# eight-channel-ina2128-afe.net
KiCad netlist of a schematic drawn in Altium Designer
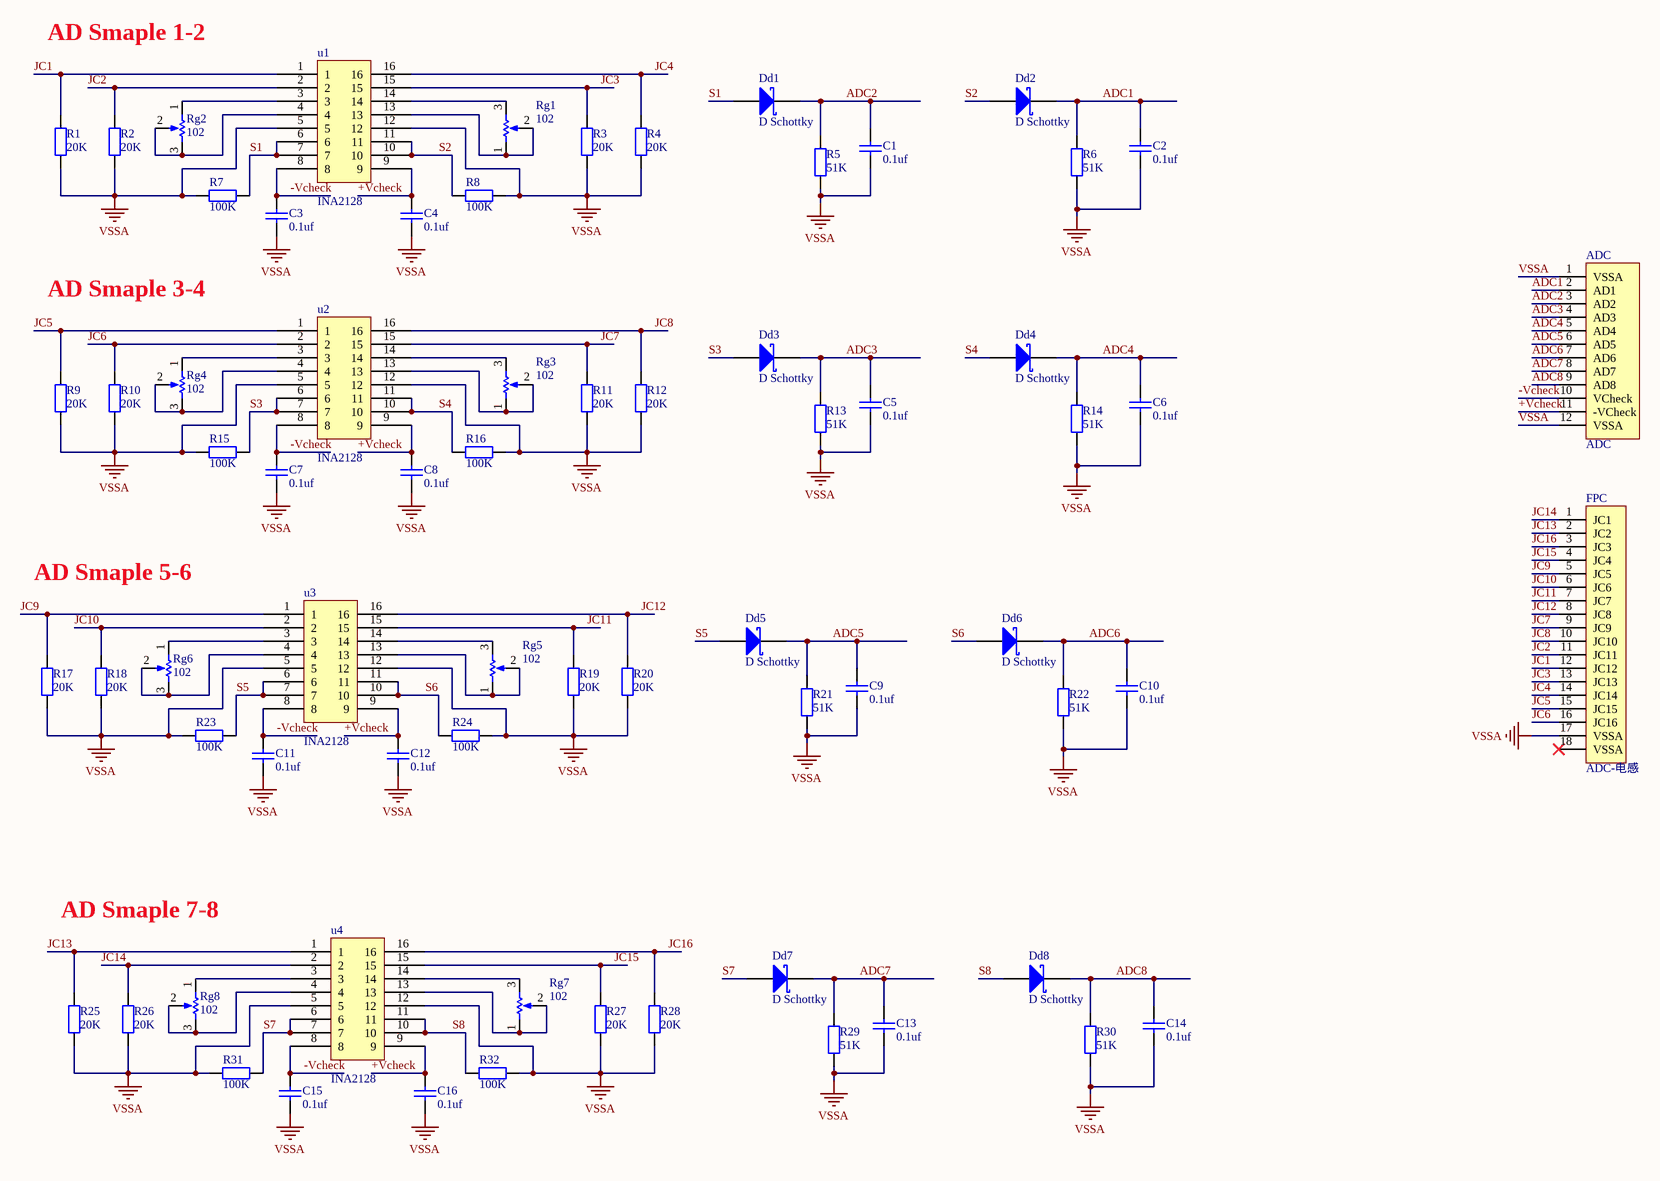
[diagram p0: eight-channel-ina2128-afe.SchDoc]

(export (version "E")
  (design (tool "Eeschema 10.0.6"))
  (components
    (comp (ref "ADC") (value "ADC") (footprint "FPC0.5 2H-WS-12P") (libsource (lib "my_DXP") (part "ADC")))
    (comp (ref "C1") (value "0.1uf") (footprint "LC-0603_C") (libsource (lib "my_DXP") (part "Cap")))
    (comp (ref "C2") (value "0.1uf") (footprint "LC-0603_C") (libsource (lib "my_DXP") (part "Cap")))
    (comp (ref "C3") (value "0.1uf") (footprint "LC-0603_C") (libsource (lib "my_DXP") (part "Cap")))
    (comp (ref "C4") (value "0.1uf") (footprint "LC-0603_C") (libsource (lib "my_DXP") (part "Cap")))
    (comp (ref "C5") (value "0.1uf") (footprint "LC-0603_C") (libsource (lib "my_DXP") (part "Cap")))
    (comp (ref "C6") (value "0.1uf") (footprint "LC-0603_C") (libsource (lib "my_DXP") (part "Cap")))
    (comp (ref "C7") (value "0.1uf") (footprint "LC-0603_C") (libsource (lib "my_DXP") (part "Cap")))
    (comp (ref "C8") (value "0.1uf") (footprint "LC-0603_C") (libsource (lib "my_DXP") (part "Cap")))
    (comp (ref "C9") (value "0.1uf") (footprint "LC-0603_C") (libsource (lib "my_DXP") (part "Cap")))
    (comp (ref "C10") (value "0.1uf") (footprint "LC-0603_C") (libsource (lib "my_DXP") (part "Cap")))
    (comp (ref "C11") (value "0.1uf") (footprint "LC-0603_C") (libsource (lib "my_DXP") (part "Cap")))
    (comp (ref "C12") (value "0.1uf") (footprint "LC-0603_C") (libsource (lib "my_DXP") (part "Cap")))
    (comp (ref "C13") (value "0.1uf") (footprint "LC-0603_C") (libsource (lib "my_DXP") (part "Cap")))
    (comp (ref "C14") (value "0.1uf") (footprint "LC-0603_C") (libsource (lib "my_DXP") (part "Cap")))
    (comp (ref "C15") (value "0.1uf") (footprint "LC-0603_C") (libsource (lib "my_DXP") (part "Cap")))
    (comp (ref "C16") (value "0.1uf") (footprint "LC-0603_C") (libsource (lib "my_DXP") (part "Cap")))
    (comp (ref "Dd1")
      (value "D Schottky")
      (footprint "SOD-323")
      (description "Schottky Diode")
      (fields (field (name "PUBLISHER") "Altium Limited"))
      (libsource (lib "my_DXP") (part "D Schottky"))
    )
    (comp (ref "Dd2")
      (value "D Schottky")
      (footprint "SOD-323")
      (description "Schottky Diode")
      (fields (field (name "PUBLISHER") "Altium Limited"))
      (libsource (lib "my_DXP") (part "D Schottky"))
    )
    (comp (ref "Dd3")
      (value "D Schottky")
      (footprint "SOD-323")
      (description "Schottky Diode")
      (fields (field (name "PUBLISHER") "Altium Limited"))
      (libsource (lib "my_DXP") (part "D Schottky"))
    )
    (comp (ref "Dd4")
      (value "D Schottky")
      (footprint "SOD-323")
      (description "Schottky Diode")
      (fields (field (name "PUBLISHER") "Altium Limited"))
      (libsource (lib "my_DXP") (part "D Schottky"))
    )
    (comp (ref "Dd5")
      (value "D Schottky")
      (footprint "SOD-323")
      (description "Schottky Diode")
      (fields (field (name "PUBLISHER") "Altium Limited"))
      (libsource (lib "my_DXP") (part "D Schottky"))
    )
    (comp (ref "Dd6")
      (value "D Schottky")
      (footprint "SOD-323")
      (description "Schottky Diode")
      (fields (field (name "PUBLISHER") "Altium Limited"))
      (libsource (lib "my_DXP") (part "D Schottky"))
    )
    (comp (ref "Dd7")
      (value "D Schottky")
      (footprint "SOD-323")
      (description "Schottky Diode")
      (fields (field (name "PUBLISHER") "Altium Limited"))
      (libsource (lib "my_DXP") (part "D Schottky"))
    )
    (comp (ref "Dd8")
      (value "D Schottky")
      (footprint "SOD-323")
      (description "Schottky Diode")
      (fields (field (name "PUBLISHER") "Altium Limited"))
      (libsource (lib "my_DXP") (part "D Schottky"))
    )
    (comp (ref "FPC") (value "ADC-电感") (footprint "fpc_0.5_16pin") (libsource (lib "my_DXP") (part "ADC-电感")))
    (comp (ref "R1")
      (value "20K")
      (footprint "LC-0603_R")
      (description "Resistor")
      (fields (field (name "Comment") "20k") (field (name "PUBLISHER") "Altium Limited"))
      (libsource (lib "my_DXP") (part "Res"))
    )
    (comp (ref "R2")
      (value "20K")
      (footprint "LC-0603_R")
      (description "Resistor")
      (fields (field (name "Comment") "20k") (field (name "PUBLISHER") "Altium Limited"))
      (libsource (lib "my_DXP") (part "Res"))
    )
    (comp (ref "R3")
      (value "20K")
      (footprint "LC-0603_R")
      (description "Resistor")
      (fields (field (name "Comment") "20k") (field (name "PUBLISHER") "Altium Limited"))
      (libsource (lib "my_DXP") (part "Res"))
    )
    (comp (ref "R4")
      (value "20K")
      (footprint "LC-0603_R")
      (description "Resistor")
      (fields (field (name "Comment") "20k") (field (name "PUBLISHER") "Altium Limited"))
      (libsource (lib "my_DXP") (part "Res"))
    )
    (comp (ref "R5")
      (value "51K")
      (footprint "LC-0603_R")
      (description "Resistor")
      (fields (field (name "Comment") "20k") (field (name "PUBLISHER") "Altium Limited"))
      (libsource (lib "my_DXP") (part "Res"))
    )
    (comp (ref "R6")
      (value "51K")
      (footprint "LC-0603_R")
      (description "Resistor")
      (fields (field (name "Comment") "20k") (field (name "PUBLISHER") "Altium Limited"))
      (libsource (lib "my_DXP") (part "Res"))
    )
    (comp (ref "R7")
      (value "100K")
      (footprint "LC-0603_R")
      (description "Resistor")
      (fields (field (name "Comment") "100k") (field (name "PUBLISHER") "Altium Limited"))
      (libsource (lib "") (part "Res_1"))
    )
    (comp (ref "R8")
      (value "100K")
      (footprint "LC-0603_R")
      (description "Resistor")
      (fields (field (name "Comment") "100k") (field (name "PUBLISHER") "Altium Limited"))
      (libsource (lib "") (part "Res_1"))
    )
    (comp (ref "R9")
      (value "20K")
      (footprint "LC-0603_R")
      (description "Resistor")
      (fields (field (name "Comment") "20k") (field (name "PUBLISHER") "Altium Limited"))
      (libsource (lib "my_DXP") (part "Res"))
    )
    (comp (ref "R10")
      (value "20K")
      (footprint "LC-0603_R")
      (description "Resistor")
      (fields (field (name "Comment") "20k") (field (name "PUBLISHER") "Altium Limited"))
      (libsource (lib "my_DXP") (part "Res"))
    )
    (comp (ref "R11")
      (value "20K")
      (footprint "LC-0603_R")
      (description "Resistor")
      (fields (field (name "Comment") "20k") (field (name "PUBLISHER") "Altium Limited"))
      (libsource (lib "my_DXP") (part "Res"))
    )
    (comp (ref "R12")
      (value "20K")
      (footprint "LC-0603_R")
      (description "Resistor")
      (fields (field (name "Comment") "20k") (field (name "PUBLISHER") "Altium Limited"))
      (libsource (lib "my_DXP") (part "Res"))
    )
    (comp (ref "R13")
      (value "51K")
      (footprint "LC-0603_R")
      (description "Resistor")
      (fields (field (name "Comment") "20k") (field (name "PUBLISHER") "Altium Limited"))
      (libsource (lib "my_DXP") (part "Res"))
    )
    (comp (ref "R14")
      (value "51K")
      (footprint "LC-0603_R")
      (description "Resistor")
      (fields (field (name "Comment") "20k") (field (name "PUBLISHER") "Altium Limited"))
      (libsource (lib "my_DXP") (part "Res"))
    )
    (comp (ref "R15")
      (value "100K")
      (footprint "LC-0603_R")
      (description "Resistor")
      (fields (field (name "Comment") "100k") (field (name "PUBLISHER") "Altium Limited"))
      (libsource (lib "") (part "Res_1"))
    )
    (comp (ref "R16")
      (value "100K")
      (footprint "LC-0603_R")
      (description "Resistor")
      (fields (field (name "Comment") "100k") (field (name "PUBLISHER") "Altium Limited"))
      (libsource (lib "") (part "Res_1"))
    )
    (comp (ref "R17")
      (value "20K")
      (footprint "LC-0603_R")
      (description "Resistor")
      (fields (field (name "Comment") "20k") (field (name "PUBLISHER") "Altium Limited"))
      (libsource (lib "my_DXP") (part "Res"))
    )
    (comp (ref "R18")
      (value "20K")
      (footprint "LC-0603_R")
      (description "Resistor")
      (fields (field (name "Comment") "20k") (field (name "PUBLISHER") "Altium Limited"))
      (libsource (lib "my_DXP") (part "Res"))
    )
    (comp (ref "R19")
      (value "20K")
      (footprint "LC-0603_R")
      (description "Resistor")
      (fields (field (name "Comment") "20k") (field (name "PUBLISHER") "Altium Limited"))
      (libsource (lib "my_DXP") (part "Res"))
    )
    (comp (ref "R20")
      (value "20K")
      (footprint "LC-0603_R")
      (description "Resistor")
      (fields (field (name "Comment") "20k") (field (name "PUBLISHER") "Altium Limited"))
      (libsource (lib "my_DXP") (part "Res"))
    )
    (comp (ref "R21")
      (value "51K")
      (footprint "LC-0603_R")
      (description "Resistor")
      (fields (field (name "Comment") "20k") (field (name "PUBLISHER") "Altium Limited"))
      (libsource (lib "my_DXP") (part "Res"))
    )
    (comp (ref "R22")
      (value "51K")
      (footprint "LC-0603_R")
      (description "Resistor")
      (fields (field (name "Comment") "20k") (field (name "PUBLISHER") "Altium Limited"))
      (libsource (lib "my_DXP") (part "Res"))
    )
    (comp (ref "R23")
      (value "100K")
      (footprint "LC-0603_R")
      (description "Resistor")
      (fields (field (name "Comment") "100k") (field (name "PUBLISHER") "Altium Limited"))
      (libsource (lib "") (part "Res_1"))
    )
    (comp (ref "R24")
      (value "100K")
      (footprint "LC-0603_R")
      (description "Resistor")
      (fields (field (name "Comment") "100k") (field (name "PUBLISHER") "Altium Limited"))
      (libsource (lib "") (part "Res_1"))
    )
    (comp (ref "R25")
      (value "20K")
      (footprint "LC-0603_R")
      (description "Resistor")
      (fields (field (name "Comment") "20k") (field (name "PUBLISHER") "Altium Limited"))
      (libsource (lib "my_DXP") (part "Res"))
    )
    (comp (ref "R26")
      (value "20K")
      (footprint "LC-0603_R")
      (description "Resistor")
      (fields (field (name "Comment") "20k") (field (name "PUBLISHER") "Altium Limited"))
      (libsource (lib "my_DXP") (part "Res"))
    )
    (comp (ref "R27")
      (value "20K")
      (footprint "LC-0603_R")
      (description "Resistor")
      (fields (field (name "Comment") "20k") (field (name "PUBLISHER") "Altium Limited"))
      (libsource (lib "my_DXP") (part "Res"))
    )
    (comp (ref "R28")
      (value "20K")
      (footprint "LC-0603_R")
      (description "Resistor")
      (fields (field (name "Comment") "20k") (field (name "PUBLISHER") "Altium Limited"))
      (libsource (lib "my_DXP") (part "Res"))
    )
    (comp (ref "R29")
      (value "51K")
      (footprint "LC-0603_R")
      (description "Resistor")
      (fields (field (name "Comment") "20k") (field (name "PUBLISHER") "Altium Limited"))
      (libsource (lib "my_DXP") (part "Res"))
    )
    (comp (ref "R30")
      (value "51K")
      (footprint "LC-0603_R")
      (description "Resistor")
      (fields (field (name "Comment") "20k") (field (name "PUBLISHER") "Altium Limited"))
      (libsource (lib "my_DXP") (part "Res"))
    )
    (comp (ref "R31")
      (value "100K")
      (footprint "LC-0603_R")
      (description "Resistor")
      (fields (field (name "Comment") "100k") (field (name "PUBLISHER") "Altium Limited"))
      (libsource (lib "") (part "Res_1"))
    )
    (comp (ref "R32")
      (value "100K")
      (footprint "LC-0603_R")
      (description "Resistor")
      (fields (field (name "Comment") "100k") (field (name "PUBLISHER") "Altium Limited"))
      (libsource (lib "") (part "Res_1"))
    )
    (comp (ref "Rg1")
      (value "102")
      (footprint "精密电位器")
      (description "Potentiometer")
      (fields (field (name "PUBLISHER") "Altium Limited"))
      (libsource (lib "my_DXP") (part "RPot"))
    )
    (comp (ref "Rg2")
      (value "102")
      (footprint "精密电位器")
      (description "Potentiometer")
      (fields (field (name "PUBLISHER") "Altium Limited"))
      (libsource (lib "my_DXP") (part "RPot"))
    )
    (comp (ref "Rg3")
      (value "102")
      (footprint "精密电位器")
      (description "Potentiometer")
      (fields (field (name "PUBLISHER") "Altium Limited"))
      (libsource (lib "my_DXP") (part "RPot"))
    )
    (comp (ref "Rg4")
      (value "102")
      (footprint "精密电位器")
      (description "Potentiometer")
      (fields (field (name "PUBLISHER") "Altium Limited"))
      (libsource (lib "my_DXP") (part "RPot"))
    )
    (comp (ref "Rg5")
      (value "102")
      (footprint "精密电位器")
      (description "Potentiometer")
      (fields (field (name "PUBLISHER") "Altium Limited"))
      (libsource (lib "my_DXP") (part "RPot"))
    )
    (comp (ref "Rg6")
      (value "102")
      (footprint "精密电位器")
      (description "Potentiometer")
      (fields (field (name "PUBLISHER") "Altium Limited"))
      (libsource (lib "my_DXP") (part "RPot"))
    )
    (comp (ref "Rg7")
      (value "102")
      (footprint "精密电位器")
      (description "Potentiometer")
      (fields (field (name "PUBLISHER") "Altium Limited"))
      (libsource (lib "my_DXP") (part "RPot"))
    )
    (comp (ref "Rg8")
      (value "102")
      (footprint "精密电位器")
      (description "Potentiometer")
      (fields (field (name "PUBLISHER") "Altium Limited"))
      (libsource (lib "my_DXP") (part "RPot"))
    )
    (comp (ref "u1") (value "INA2128") (footprint "INA2128") (libsource (lib "my_DXP") (part "INA2128")))
    (comp (ref "u2") (value "INA2128") (footprint "INA2128") (libsource (lib "my_DXP") (part "INA2128")))
    (comp (ref "u3") (value "INA2128") (footprint "INA2128") (libsource (lib "my_DXP") (part "INA2128")))
    (comp (ref "u4") (value "INA2128") (footprint "INA2128") (libsource (lib "my_DXP") (part "INA2128")))
  )
  (nets
    (net (code "1") (name "/+Vcheck") (class "Default")
      (node (ref "ADC") (pin "11") (pinfunction "-VCheck_11") (pintype "passive"))
      (node (ref "C12") (pin "2") (pinfunction "2_2") (pintype "passive"))
      (node (ref "C16") (pin "2") (pinfunction "2_2") (pintype "passive"))
      (node (ref "C4") (pin "2") (pinfunction "2_2") (pintype "passive"))
      (node (ref "C8") (pin "2") (pinfunction "2_2") (pintype "passive"))
      (node (ref "u1") (pin "9") (pinfunction "9_9") (pintype "passive"))
      (node (ref "u2") (pin "9") (pinfunction "9_9") (pintype "passive"))
      (node (ref "u3") (pin "9") (pinfunction "9_9") (pintype "passive"))
      (node (ref "u4") (pin "9") (pinfunction "9_9") (pintype "passive"))
    )
    (net (code "2") (name "/-Vcheck") (class "Default")
      (node (ref "ADC") (pin "10") (pinfunction "VCheck_10") (pintype "passive"))
      (node (ref "C11") (pin "2") (pinfunction "2_2") (pintype "passive"))
      (node (ref "C15") (pin "2") (pinfunction "2_2") (pintype "passive"))
      (node (ref "C3") (pin "2") (pinfunction "2_2") (pintype "passive"))
      (node (ref "C7") (pin "2") (pinfunction "2_2") (pintype "passive"))
      (node (ref "u1") (pin "8") (pinfunction "8_8") (pintype "passive"))
      (node (ref "u2") (pin "8") (pinfunction "8_8") (pintype "passive"))
      (node (ref "u3") (pin "8") (pinfunction "8_8") (pintype "passive"))
      (node (ref "u4") (pin "8") (pinfunction "8_8") (pintype "passive"))
    )
    (net (code "3") (name "/ADC1") (class "Default")
      (node (ref "ADC") (pin "2") (pinfunction "AD1_2") (pintype "passive"))
      (node (ref "C2") (pin "2") (pinfunction "2_2") (pintype "passive"))
      (node (ref "Dd2") (pin "2") (pinfunction "K_2") (pintype "passive"))
      (node (ref "R6") (pin "1") (pinfunction "1_1") (pintype "passive"))
    )
    (net (code "4") (name "/ADC2") (class "Default")
      (node (ref "ADC") (pin "3") (pinfunction "AD2_3") (pintype "passive"))
      (node (ref "C1") (pin "2") (pinfunction "2_2") (pintype "passive"))
      (node (ref "Dd1") (pin "2") (pinfunction "K_2") (pintype "passive"))
      (node (ref "R5") (pin "1") (pinfunction "1_1") (pintype "passive"))
    )
    (net (code "5") (name "/ADC3") (class "Default")
      (node (ref "ADC") (pin "4") (pinfunction "AD3_4") (pintype "passive"))
      (node (ref "C5") (pin "2") (pinfunction "2_2") (pintype "passive"))
      (node (ref "Dd3") (pin "2") (pinfunction "K_2") (pintype "passive"))
      (node (ref "R13") (pin "1") (pinfunction "1_1") (pintype "passive"))
    )
    (net (code "6") (name "/ADC4") (class "Default")
      (node (ref "ADC") (pin "5") (pinfunction "AD4_5") (pintype "passive"))
      (node (ref "C6") (pin "2") (pinfunction "2_2") (pintype "passive"))
      (node (ref "Dd4") (pin "2") (pinfunction "K_2") (pintype "passive"))
      (node (ref "R14") (pin "1") (pinfunction "1_1") (pintype "passive"))
    )
    (net (code "7") (name "/ADC5") (class "Default")
      (node (ref "ADC") (pin "6") (pinfunction "AD5_6") (pintype "passive"))
      (node (ref "C9") (pin "2") (pinfunction "2_2") (pintype "passive"))
      (node (ref "Dd5") (pin "2") (pinfunction "K_2") (pintype "passive"))
      (node (ref "R21") (pin "1") (pinfunction "1_1") (pintype "passive"))
    )
    (net (code "8") (name "/ADC6") (class "Default")
      (node (ref "ADC") (pin "7") (pinfunction "AD6_7") (pintype "passive"))
      (node (ref "C10") (pin "2") (pinfunction "2_2") (pintype "passive"))
      (node (ref "Dd6") (pin "2") (pinfunction "K_2") (pintype "passive"))
      (node (ref "R22") (pin "1") (pinfunction "1_1") (pintype "passive"))
    )
    (net (code "9") (name "/ADC7") (class "Default")
      (node (ref "ADC") (pin "8") (pinfunction "AD7_8") (pintype "passive"))
      (node (ref "C13") (pin "2") (pinfunction "2_2") (pintype "passive"))
      (node (ref "Dd7") (pin "2") (pinfunction "K_2") (pintype "passive"))
      (node (ref "R29") (pin "1") (pinfunction "1_1") (pintype "passive"))
    )
    (net (code "10") (name "/ADC8") (class "Default")
      (node (ref "ADC") (pin "9") (pinfunction "AD8_9") (pintype "passive"))
      (node (ref "C14") (pin "2") (pinfunction "2_2") (pintype "passive"))
      (node (ref "Dd8") (pin "2") (pinfunction "K_2") (pintype "passive"))
      (node (ref "R30") (pin "1") (pinfunction "1_1") (pintype "passive"))
    )
    (net (code "11") (name "/JC1") (class "Default")
      (node (ref "FPC") (pin "12") (pinfunction "JC12_12") (pintype "passive"))
      (node (ref "R1") (pin "1") (pinfunction "1_1") (pintype "passive"))
      (node (ref "u1") (pin "1") (pinfunction "1_1") (pintype "passive"))
    )
    (net (code "12") (name "/JC2") (class "Default")
      (node (ref "FPC") (pin "11") (pinfunction "JC11_11") (pintype "passive"))
      (node (ref "R2") (pin "1") (pinfunction "1_1") (pintype "passive"))
      (node (ref "u1") (pin "2") (pinfunction "2_2") (pintype "passive"))
    )
    (net (code "13") (name "/JC3") (class "Default")
      (node (ref "FPC") (pin "13") (pinfunction "JC13_13") (pintype "passive"))
      (node (ref "R3") (pin "1") (pinfunction "1_1") (pintype "passive"))
      (node (ref "u1") (pin "15") (pinfunction "15_15") (pintype "passive"))
    )
    (net (code "14") (name "/JC4") (class "Default")
      (node (ref "FPC") (pin "14") (pinfunction "JC14_14") (pintype "passive"))
      (node (ref "R4") (pin "1") (pinfunction "1_1") (pintype "passive"))
      (node (ref "u1") (pin "16") (pinfunction "16_16") (pintype "passive"))
    )
    (net (code "15") (name "/JC5") (class "Default")
      (node (ref "FPC") (pin "15") (pinfunction "JC15_15") (pintype "passive"))
      (node (ref "R9") (pin "1") (pinfunction "1_1") (pintype "passive"))
      (node (ref "u2") (pin "1") (pinfunction "1_1") (pintype "passive"))
    )
    (net (code "16") (name "/JC6") (class "Default")
      (node (ref "FPC") (pin "16") (pinfunction "JC16_16") (pintype "passive"))
      (node (ref "R10") (pin "1") (pinfunction "1_1") (pintype "passive"))
      (node (ref "u2") (pin "2") (pinfunction "2_2") (pintype "passive"))
    )
    (net (code "17") (name "/JC7") (class "Default")
      (node (ref "FPC") (pin "9") (pinfunction "JC9_9") (pintype "passive"))
      (node (ref "R11") (pin "1") (pinfunction "1_1") (pintype "passive"))
      (node (ref "u2") (pin "15") (pinfunction "15_15") (pintype "passive"))
    )
    (net (code "18") (name "/JC8") (class "Default")
      (node (ref "FPC") (pin "10") (pinfunction "JC10_10") (pintype "passive"))
      (node (ref "R12") (pin "1") (pinfunction "1_1") (pintype "passive"))
      (node (ref "u2") (pin "16") (pinfunction "16_16") (pintype "passive"))
    )
    (net (code "19") (name "/JC9") (class "Default")
      (node (ref "FPC") (pin "5") (pinfunction "JC5_5") (pintype "passive"))
      (node (ref "R17") (pin "1") (pinfunction "1_1") (pintype "passive"))
      (node (ref "u3") (pin "1") (pinfunction "1_1") (pintype "passive"))
    )
    (net (code "20") (name "/JC10") (class "Default")
      (node (ref "FPC") (pin "6") (pinfunction "JC6_6") (pintype "passive"))
      (node (ref "R18") (pin "1") (pinfunction "1_1") (pintype "passive"))
      (node (ref "u3") (pin "2") (pinfunction "2_2") (pintype "passive"))
    )
    (net (code "21") (name "/JC11") (class "Default")
      (node (ref "FPC") (pin "7") (pinfunction "JC7_7") (pintype "passive"))
      (node (ref "R19") (pin "1") (pinfunction "1_1") (pintype "passive"))
      (node (ref "u3") (pin "15") (pinfunction "15_15") (pintype "passive"))
    )
    (net (code "22") (name "/JC12") (class "Default")
      (node (ref "FPC") (pin "8") (pinfunction "JC8_8") (pintype "passive"))
      (node (ref "R20") (pin "1") (pinfunction "1_1") (pintype "passive"))
      (node (ref "u3") (pin "16") (pinfunction "16_16") (pintype "passive"))
    )
    (net (code "23") (name "/JC13") (class "Default")
      (node (ref "FPC") (pin "2") (pinfunction "JC2_2") (pintype "passive"))
      (node (ref "R25") (pin "1") (pinfunction "1_1") (pintype "passive"))
      (node (ref "u4") (pin "1") (pinfunction "1_1") (pintype "passive"))
    )
    (net (code "24") (name "/JC14") (class "Default")
      (node (ref "FPC") (pin "1") (pinfunction "JC1_1") (pintype "passive"))
      (node (ref "R26") (pin "1") (pinfunction "1_1") (pintype "passive"))
      (node (ref "u4") (pin "2") (pinfunction "2_2") (pintype "passive"))
    )
    (net (code "25") (name "/JC15") (class "Default")
      (node (ref "FPC") (pin "4") (pinfunction "JC4_4") (pintype "passive"))
      (node (ref "R27") (pin "1") (pinfunction "1_1") (pintype "passive"))
      (node (ref "u4") (pin "15") (pinfunction "15_15") (pintype "passive"))
    )
    (net (code "26") (name "/JC16") (class "Default")
      (node (ref "FPC") (pin "3") (pinfunction "JC3_3") (pintype "passive"))
      (node (ref "R28") (pin "1") (pinfunction "1_1") (pintype "passive"))
      (node (ref "u4") (pin "16") (pinfunction "16_16") (pintype "passive"))
    )
    (net (code "27") (name "/S1") (class "Default")
      (node (ref "Dd1") (pin "1") (pinfunction "A_1") (pintype "passive"))
      (node (ref "R7") (pin "1") (pinfunction "1_1") (pintype "passive"))
      (node (ref "u1") (pin "6") (pinfunction "6_6") (pintype "passive"))
      (node (ref "u1") (pin "7") (pinfunction "7_7") (pintype "passive"))
    )
    (net (code "28") (name "/S2") (class "Default")
      (node (ref "Dd2") (pin "1") (pinfunction "A_1") (pintype "passive"))
      (node (ref "R8") (pin "2") (pinfunction "2_2") (pintype "passive"))
      (node (ref "u1") (pin "10") (pinfunction "10_10") (pintype "passive"))
      (node (ref "u1") (pin "11") (pinfunction "11_11") (pintype "passive"))
    )
    (net (code "29") (name "/S3") (class "Default")
      (node (ref "Dd3") (pin "1") (pinfunction "A_1") (pintype "passive"))
      (node (ref "R15") (pin "1") (pinfunction "1_1") (pintype "passive"))
      (node (ref "u2") (pin "6") (pinfunction "6_6") (pintype "passive"))
      (node (ref "u2") (pin "7") (pinfunction "7_7") (pintype "passive"))
    )
    (net (code "30") (name "/S4") (class "Default")
      (node (ref "Dd4") (pin "1") (pinfunction "A_1") (pintype "passive"))
      (node (ref "R16") (pin "2") (pinfunction "2_2") (pintype "passive"))
      (node (ref "u2") (pin "10") (pinfunction "10_10") (pintype "passive"))
      (node (ref "u2") (pin "11") (pinfunction "11_11") (pintype "passive"))
    )
    (net (code "31") (name "/S5") (class "Default")
      (node (ref "Dd5") (pin "1") (pinfunction "A_1") (pintype "passive"))
      (node (ref "R23") (pin "1") (pinfunction "1_1") (pintype "passive"))
      (node (ref "u3") (pin "6") (pinfunction "6_6") (pintype "passive"))
      (node (ref "u3") (pin "7") (pinfunction "7_7") (pintype "passive"))
    )
    (net (code "32") (name "/S6") (class "Default")
      (node (ref "Dd6") (pin "1") (pinfunction "A_1") (pintype "passive"))
      (node (ref "R24") (pin "2") (pinfunction "2_2") (pintype "passive"))
      (node (ref "u3") (pin "10") (pinfunction "10_10") (pintype "passive"))
      (node (ref "u3") (pin "11") (pinfunction "11_11") (pintype "passive"))
    )
    (net (code "33") (name "/S7") (class "Default")
      (node (ref "Dd7") (pin "1") (pinfunction "A_1") (pintype "passive"))
      (node (ref "R31") (pin "1") (pinfunction "1_1") (pintype "passive"))
      (node (ref "u4") (pin "6") (pinfunction "6_6") (pintype "passive"))
      (node (ref "u4") (pin "7") (pinfunction "7_7") (pintype "passive"))
    )
    (net (code "34") (name "/S8") (class "Default")
      (node (ref "Dd8") (pin "1") (pinfunction "A_1") (pintype "passive"))
      (node (ref "R32") (pin "2") (pinfunction "2_2") (pintype "passive"))
      (node (ref "u4") (pin "10") (pinfunction "10_10") (pintype "passive"))
      (node (ref "u4") (pin "11") (pinfunction "11_11") (pintype "passive"))
    )
    (net (code "35") (name "Net-(Rg1-BOT)") (class "Default")
      (node (ref "Rg1") (pin "3") (pinfunction "BOT_3") (pintype "passive"))
      (node (ref "u1") (pin "14") (pinfunction "14_14") (pintype "passive"))
    )
    (net (code "36") (name "Net-(Rg1-TAP)") (class "Default")
      (node (ref "Rg1") (pin "1") (pinfunction "TOP_1") (pintype "passive"))
      (node (ref "Rg1") (pin "2") (pinfunction "TAP_2") (pintype "passive"))
      (node (ref "u1") (pin "13") (pinfunction "13_13") (pintype "passive"))
    )
    (net (code "37") (name "Net-(Rg2-BOT)") (class "Default")
      (node (ref "Rg2") (pin "2") (pinfunction "TAP_2") (pintype "passive"))
      (node (ref "Rg2") (pin "3") (pinfunction "BOT_3") (pintype "passive"))
      (node (ref "u1") (pin "4") (pinfunction "4_4") (pintype "passive"))
    )
    (net (code "38") (name "Net-(Rg2-TOP)") (class "Default")
      (node (ref "Rg2") (pin "1") (pinfunction "TOP_1") (pintype "passive"))
      (node (ref "u1") (pin "3") (pinfunction "3_3") (pintype "passive"))
    )
    (net (code "39") (name "Net-(Rg3-BOT)") (class "Default")
      (node (ref "Rg3") (pin "3") (pinfunction "BOT_3") (pintype "passive"))
      (node (ref "u2") (pin "14") (pinfunction "14_14") (pintype "passive"))
    )
    (net (code "40") (name "Net-(Rg3-TAP)") (class "Default")
      (node (ref "Rg3") (pin "1") (pinfunction "TOP_1") (pintype "passive"))
      (node (ref "Rg3") (pin "2") (pinfunction "TAP_2") (pintype "passive"))
      (node (ref "u2") (pin "13") (pinfunction "13_13") (pintype "passive"))
    )
    (net (code "41") (name "Net-(Rg4-BOT)") (class "Default")
      (node (ref "Rg4") (pin "2") (pinfunction "TAP_2") (pintype "passive"))
      (node (ref "Rg4") (pin "3") (pinfunction "BOT_3") (pintype "passive"))
      (node (ref "u2") (pin "4") (pinfunction "4_4") (pintype "passive"))
    )
    (net (code "42") (name "Net-(Rg4-TOP)") (class "Default")
      (node (ref "Rg4") (pin "1") (pinfunction "TOP_1") (pintype "passive"))
      (node (ref "u2") (pin "3") (pinfunction "3_3") (pintype "passive"))
    )
    (net (code "43") (name "Net-(Rg5-BOT)") (class "Default")
      (node (ref "Rg5") (pin "3") (pinfunction "BOT_3") (pintype "passive"))
      (node (ref "u3") (pin "14") (pinfunction "14_14") (pintype "passive"))
    )
    (net (code "44") (name "Net-(Rg5-TAP)") (class "Default")
      (node (ref "Rg5") (pin "1") (pinfunction "TOP_1") (pintype "passive"))
      (node (ref "Rg5") (pin "2") (pinfunction "TAP_2") (pintype "passive"))
      (node (ref "u3") (pin "13") (pinfunction "13_13") (pintype "passive"))
    )
    (net (code "45") (name "Net-(Rg6-BOT)") (class "Default")
      (node (ref "Rg6") (pin "2") (pinfunction "TAP_2") (pintype "passive"))
      (node (ref "Rg6") (pin "3") (pinfunction "BOT_3") (pintype "passive"))
      (node (ref "u3") (pin "4") (pinfunction "4_4") (pintype "passive"))
    )
    (net (code "46") (name "Net-(Rg6-TOP)") (class "Default")
      (node (ref "Rg6") (pin "1") (pinfunction "TOP_1") (pintype "passive"))
      (node (ref "u3") (pin "3") (pinfunction "3_3") (pintype "passive"))
    )
    (net (code "47") (name "Net-(Rg7-BOT)") (class "Default")
      (node (ref "Rg7") (pin "3") (pinfunction "BOT_3") (pintype "passive"))
      (node (ref "u4") (pin "14") (pinfunction "14_14") (pintype "passive"))
    )
    (net (code "48") (name "Net-(Rg7-TAP)") (class "Default")
      (node (ref "Rg7") (pin "1") (pinfunction "TOP_1") (pintype "passive"))
      (node (ref "Rg7") (pin "2") (pinfunction "TAP_2") (pintype "passive"))
      (node (ref "u4") (pin "13") (pinfunction "13_13") (pintype "passive"))
    )
    (net (code "49") (name "Net-(Rg8-BOT)") (class "Default")
      (node (ref "Rg8") (pin "2") (pinfunction "TAP_2") (pintype "passive"))
      (node (ref "Rg8") (pin "3") (pinfunction "BOT_3") (pintype "passive"))
      (node (ref "u4") (pin "4") (pinfunction "4_4") (pintype "passive"))
    )
    (net (code "50") (name "Net-(Rg8-TOP)") (class "Default")
      (node (ref "Rg8") (pin "1") (pinfunction "TOP_1") (pintype "passive"))
      (node (ref "u4") (pin "3") (pinfunction "3_3") (pintype "passive"))
    )
    (net (code "51") (name "VSSA") (class "Default")
      (node (ref "ADC") (pin "1") (pinfunction "VSSA_1") (pintype "passive"))
      (node (ref "ADC") (pin "12") (pinfunction "VSSA_12") (pintype "passive"))
      (node (ref "C1") (pin "1") (pinfunction "1_1") (pintype "passive"))
      (node (ref "C10") (pin "1") (pinfunction "1_1") (pintype "passive"))
      (node (ref "C11") (pin "1") (pinfunction "1_1") (pintype "passive"))
      (node (ref "C12") (pin "1") (pinfunction "1_1") (pintype "passive"))
      (node (ref "C13") (pin "1") (pinfunction "1_1") (pintype "passive"))
      (node (ref "C14") (pin "1") (pinfunction "1_1") (pintype "passive"))
      (node (ref "C15") (pin "1") (pinfunction "1_1") (pintype "passive"))
      (node (ref "C16") (pin "1") (pinfunction "1_1") (pintype "passive"))
      (node (ref "C2") (pin "1") (pinfunction "1_1") (pintype "passive"))
      (node (ref "C3") (pin "1") (pinfunction "1_1") (pintype "passive"))
      (node (ref "C4") (pin "1") (pinfunction "1_1") (pintype "passive"))
      (node (ref "C5") (pin "1") (pinfunction "1_1") (pintype "passive"))
      (node (ref "C6") (pin "1") (pinfunction "1_1") (pintype "passive"))
      (node (ref "C7") (pin "1") (pinfunction "1_1") (pintype "passive"))
      (node (ref "C8") (pin "1") (pinfunction "1_1") (pintype "passive"))
      (node (ref "C9") (pin "1") (pinfunction "1_1") (pintype "passive"))
      (node (ref "FPC") (pin "17") (pinfunction "VSSA_17") (pintype "passive"))
      (node (ref "R1") (pin "2") (pinfunction "2_2") (pintype "passive"))
      (node (ref "R10") (pin "2") (pinfunction "2_2") (pintype "passive"))
      (node (ref "R11") (pin "2") (pinfunction "2_2") (pintype "passive"))
      (node (ref "R12") (pin "2") (pinfunction "2_2") (pintype "passive"))
      (node (ref "R13") (pin "2") (pinfunction "2_2") (pintype "passive"))
      (node (ref "R14") (pin "2") (pinfunction "2_2") (pintype "passive"))
      (node (ref "R15") (pin "2") (pinfunction "2_2") (pintype "passive"))
      (node (ref "R16") (pin "1") (pinfunction "1_1") (pintype "passive"))
      (node (ref "R17") (pin "2") (pinfunction "2_2") (pintype "passive"))
      (node (ref "R18") (pin "2") (pinfunction "2_2") (pintype "passive"))
      (node (ref "R19") (pin "2") (pinfunction "2_2") (pintype "passive"))
      (node (ref "R2") (pin "2") (pinfunction "2_2") (pintype "passive"))
      (node (ref "R20") (pin "2") (pinfunction "2_2") (pintype "passive"))
      (node (ref "R21") (pin "2") (pinfunction "2_2") (pintype "passive"))
      (node (ref "R22") (pin "2") (pinfunction "2_2") (pintype "passive"))
      (node (ref "R23") (pin "2") (pinfunction "2_2") (pintype "passive"))
      (node (ref "R24") (pin "1") (pinfunction "1_1") (pintype "passive"))
      (node (ref "R25") (pin "2") (pinfunction "2_2") (pintype "passive"))
      (node (ref "R26") (pin "2") (pinfunction "2_2") (pintype "passive"))
      (node (ref "R27") (pin "2") (pinfunction "2_2") (pintype "passive"))
      (node (ref "R28") (pin "2") (pinfunction "2_2") (pintype "passive"))
      (node (ref "R29") (pin "2") (pinfunction "2_2") (pintype "passive"))
      (node (ref "R3") (pin "2") (pinfunction "2_2") (pintype "passive"))
      (node (ref "R30") (pin "2") (pinfunction "2_2") (pintype "passive"))
      (node (ref "R31") (pin "2") (pinfunction "2_2") (pintype "passive"))
      (node (ref "R32") (pin "1") (pinfunction "1_1") (pintype "passive"))
      (node (ref "R4") (pin "2") (pinfunction "2_2") (pintype "passive"))
      (node (ref "R5") (pin "2") (pinfunction "2_2") (pintype "passive"))
      (node (ref "R6") (pin "2") (pinfunction "2_2") (pintype "passive"))
      (node (ref "R7") (pin "2") (pinfunction "2_2") (pintype "passive"))
      (node (ref "R8") (pin "1") (pinfunction "1_1") (pintype "passive"))
      (node (ref "R9") (pin "2") (pinfunction "2_2") (pintype "passive"))
      (node (ref "u1") (pin "12") (pinfunction "12_12") (pintype "passive"))
      (node (ref "u1") (pin "5") (pinfunction "5_5") (pintype "passive"))
      (node (ref "u2") (pin "12") (pinfunction "12_12") (pintype "passive"))
      (node (ref "u2") (pin "5") (pinfunction "5_5") (pintype "passive"))
      (node (ref "u3") (pin "12") (pinfunction "12_12") (pintype "passive"))
      (node (ref "u3") (pin "5") (pinfunction "5_5") (pintype "passive"))
      (node (ref "u4") (pin "12") (pinfunction "12_12") (pintype "passive"))
      (node (ref "u4") (pin "5") (pinfunction "5_5") (pintype "passive"))
    )
    (net (code "52") (name "unconnected-(FPC-VSSA-Pad18)") (class "Default")
      (node (ref "FPC") (pin "18") (pinfunction "VSSA_18") (pintype "passive+no_connect"))
    )
  )
)
